# Laser_Tanks_Motherboard_V4.net
KiCad netlist of a schematic drawn in EasyEDA Pro
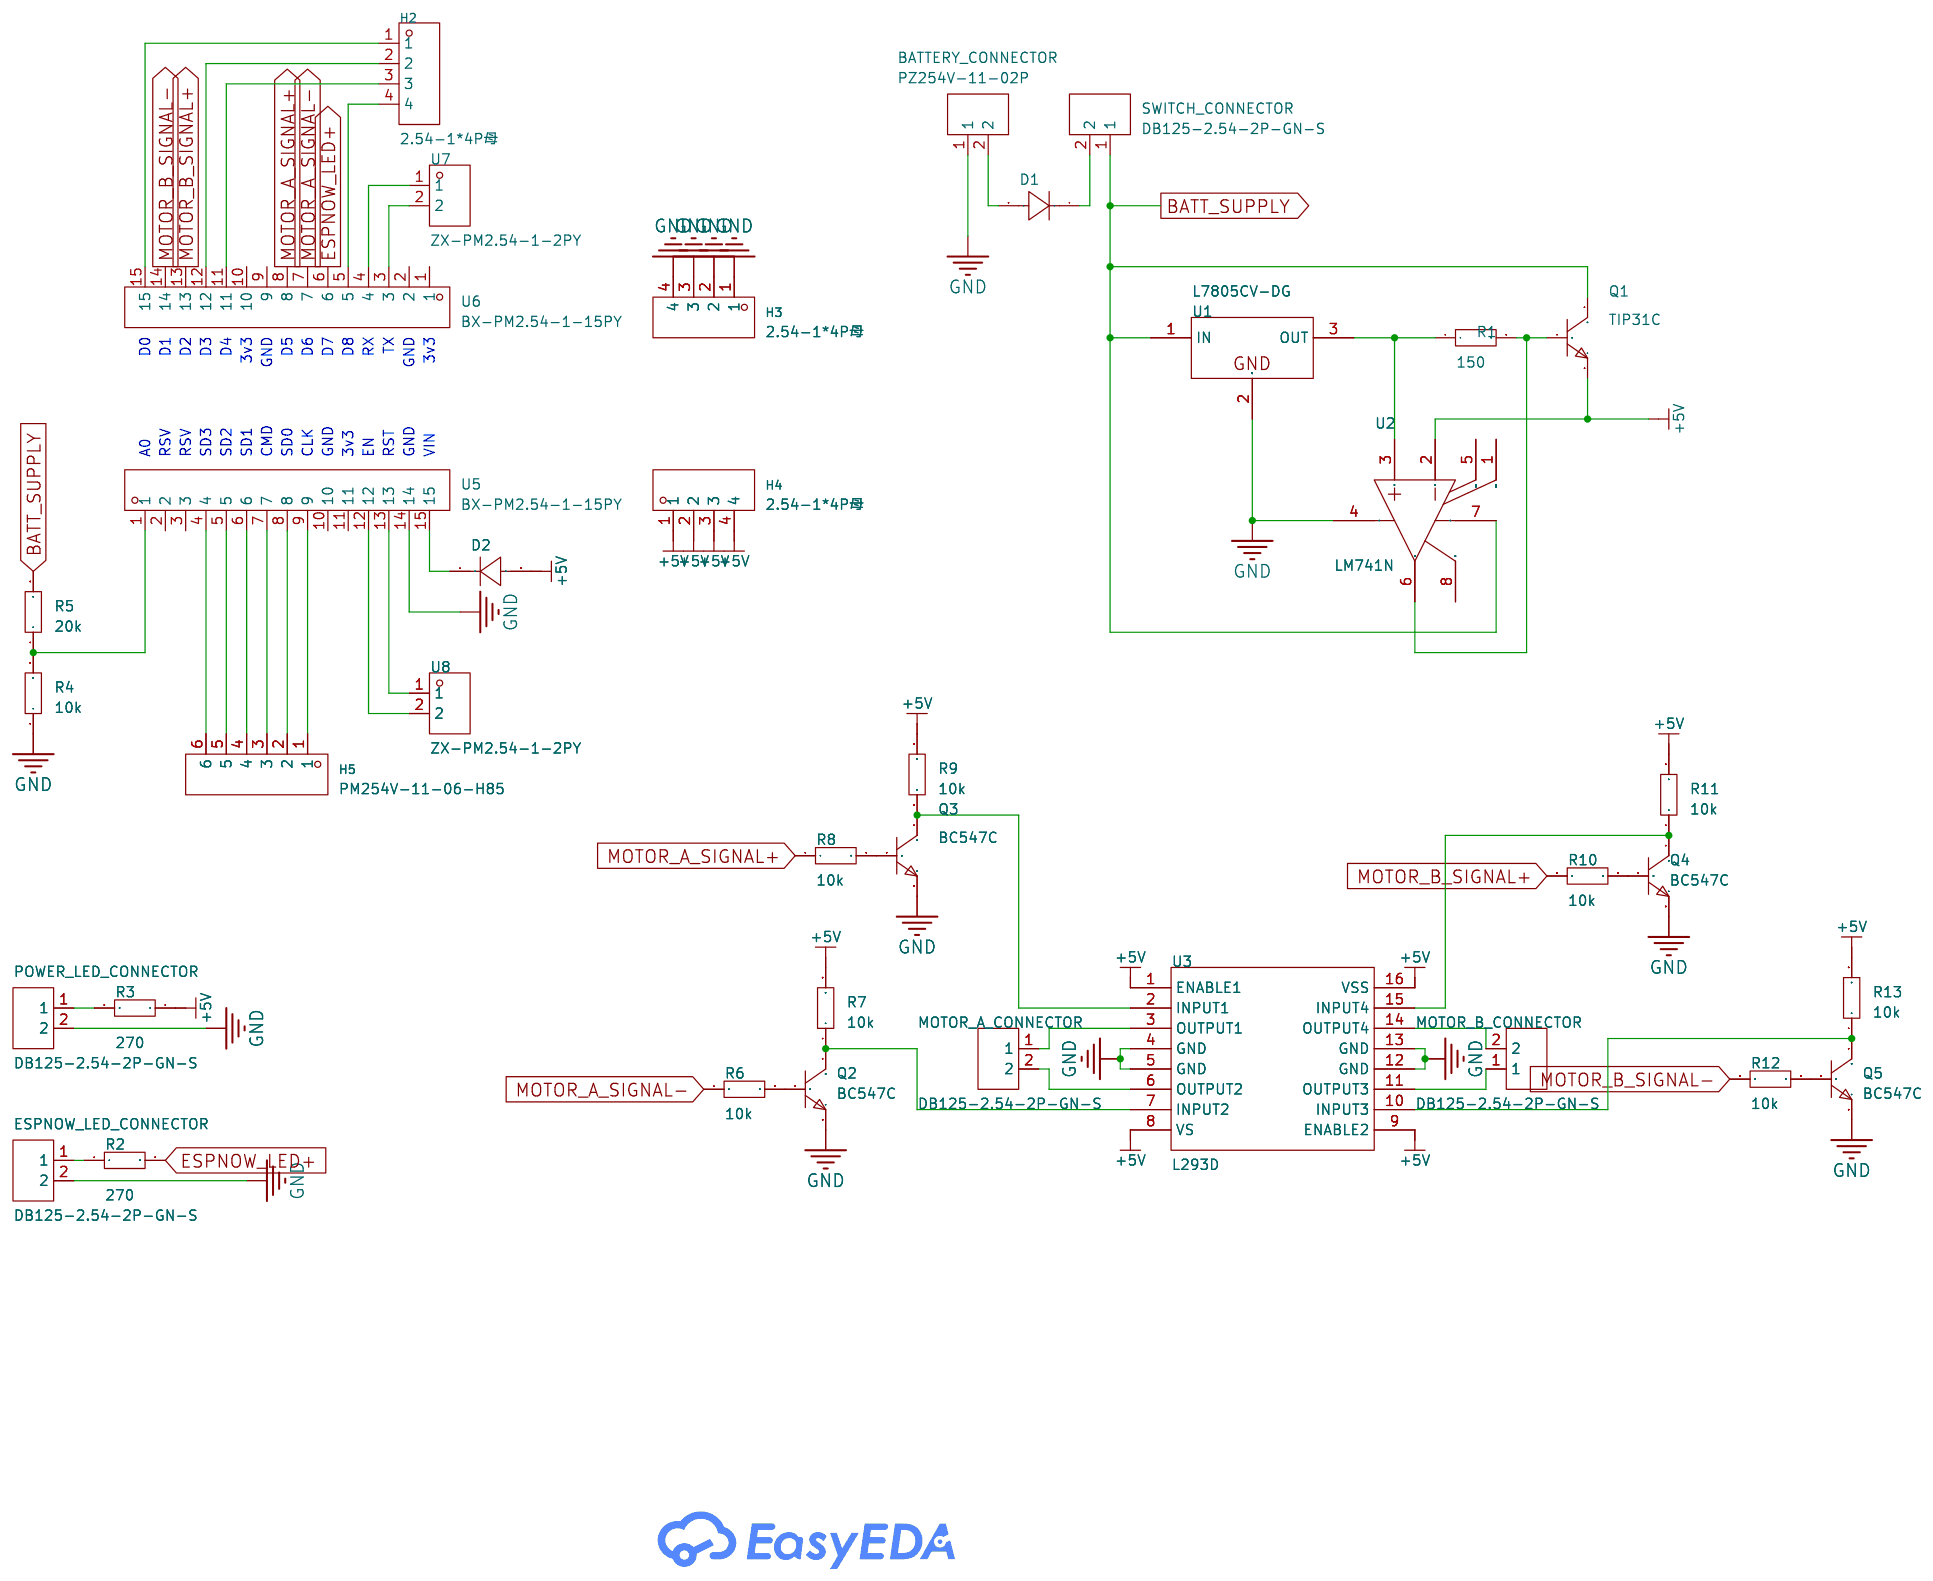
[diagram p0: schematic sheet]

(export (version "E")
  (design (tool "Eeschema 10.0.6"))
  (components
    (comp (ref "BATTERY_CONNECTOR")
      (value "PZ254V-11-02P")
      (footprint "easyedapro:HDR-TH_2P-P2.54-V-M")
      (fields (field (name "Manufacturer") "XFCN(兴飞)"))
      (libsource (lib "easyedapro") (part "PZ254V-11-02P"))
    )
    (comp (ref "D1")
      (value "~")
      (footprint "easyedapro:DO-41_BD2.4-L4.7-P8.70-D0.9-RD")
      (libsource (lib "easyedapro") (part "D_1N4007"))
    )
    (comp (ref "D2")
      (value "~")
      (footprint "easyedapro:DO-41_BD2.4-L4.7-P8.70-D0.9-RD")
      (libsource (lib "easyedapro") (part "D_1N4007"))
    )
    (comp (ref "ESPNOW_LED_CONNECTOR")
      (value "DB125-2.54-2P-GN-S")
      (footprint "easyedapro:CONN-TH_DB125-2.54-2P-GN")
      (fields (field (name "Manufacturer") "DORABO(地博电气)"))
      (libsource (lib "easyedapro") (part "DB125-2.54-2P-GN"))
    )
    (comp (ref "H2")
      (value "2.54-1*4P母")
      (footprint "easyedapro:HDR-TH_4P-P2.54-V-F")
      (fields (field (name "Manufacturer") "BOOMELE(博穆精密)"))
      (libsource (lib "easyedapro") (part "2.54-1*4P母"))
    )
    (comp (ref "H3")
      (value "2.54-1*4P母")
      (footprint "easyedapro:HDR-TH_4P-P2.54-V-F")
      (fields (field (name "Manufacturer") "BOOMELE(博穆精密)"))
      (libsource (lib "easyedapro") (part "2.54-1*4P母"))
    )
    (comp (ref "H4")
      (value "2.54-1*4P母")
      (footprint "easyedapro:HDR-TH_4P-P2.54-V-F")
      (fields (field (name "Manufacturer") "BOOMELE(博穆精密)"))
      (libsource (lib "easyedapro") (part "2.54-1*4P母"))
    )
    (comp (ref "H5")
      (value "PM254V-11-06-H85")
      (footprint "easyedapro:HDR-TH_6P-P2.54-V-F")
      (fields (field (name "Manufacturer") "XFCN(兴飞)"))
      (libsource (lib "easyedapro") (part "PM254V-11-06-H85"))
    )
    (comp (ref "MOTOR_A_CONNECTOR")
      (value "DB125-2.54-2P-GN-S")
      (footprint "easyedapro:CONN-TH_DB125-2.54-2P-GN")
      (fields (field (name "Manufacturer") "DORABO(地博电气)"))
      (libsource (lib "easyedapro") (part "DB125-2.54-2P-GN"))
    )
    (comp (ref "MOTOR_B_CONNECTOR")
      (value "DB125-2.54-2P-GN-S")
      (footprint "easyedapro:CONN-TH_DB125-2.54-2P-GN")
      (fields (field (name "Manufacturer") "DORABO(地博电气)"))
      (libsource (lib "easyedapro") (part "DB125-2.54-2P-GN"))
    )
    (comp (ref "POWER_LED_CONNECTOR")
      (value "DB125-2.54-2P-GN-S")
      (footprint "easyedapro:CONN-TH_DB125-2.54-2P-GN")
      (fields (field (name "Manufacturer") "DORABO(地博电气)"))
      (libsource (lib "easyedapro") (part "DB125-2.54-2P-GN"))
    )
    (comp (ref "Q1")
      (value "TIP31C")
      (footprint "easyedapro:TO-220-3_L10.0-W4.5-P2.54-T")
      (fields (field (name "Manufacturer") "ST(意法半导体)"))
      (libsource (lib "easyedapro") (part "TIP31C"))
    )
    (comp (ref "Q2")
      (value "BC547C")
      (footprint "easyedapro:TO-92-3_L4.9-W3.7-P1.27-L")
      (fields (field (name "Manufacturer") "LGE(鲁光)"))
      (libsource (lib "easyedapro") (part "BC547C"))
    )
    (comp (ref "Q3")
      (value "BC547C")
      (footprint "easyedapro:TO-92-3_L4.9-W3.7-P1.27-L")
      (fields (field (name "Manufacturer") "LGE(鲁光)"))
      (libsource (lib "easyedapro") (part "BC547C"))
    )
    (comp (ref "Q4")
      (value "BC547C")
      (footprint "easyedapro:TO-92-3_L4.9-W3.7-P1.27-L")
      (fields (field (name "Manufacturer") "LGE(鲁光)"))
      (libsource (lib "easyedapro") (part "BC547C"))
    )
    (comp (ref "Q5")
      (value "BC547C")
      (footprint "easyedapro:TO-92-3_L4.9-W3.7-P1.27-L")
      (fields (field (name "Manufacturer") "LGE(鲁光)"))
      (libsource (lib "easyedapro") (part "BC547C"))
    )
    (comp (ref "R1")
      (value "150")
      (footprint "easyedapro:R0603")
      (fields
        (field (name "Manufacturer Part") "MF1/4W-4.7KΩ±1% T")
        (field (name "Manufacturer") "CCO(千志电子)")
      )
      (libsource (lib "easyedapro") (part "Res"))
    )
    (comp (ref "R2")
      (value "270")
      (footprint "easyedapro:R0603")
      (fields
        (field (name "Manufacturer Part") "MF1/4W-4.7KΩ±1% T")
        (field (name "Manufacturer") "CCO(千志电子)")
      )
      (libsource (lib "easyedapro") (part "Res"))
    )
    (comp (ref "R3")
      (value "270")
      (footprint "easyedapro:R0603")
      (fields
        (field (name "Manufacturer Part") "MF1/4W-4.7KΩ±1% T")
        (field (name "Manufacturer") "CCO(千志电子)")
      )
      (libsource (lib "easyedapro") (part "Res"))
    )
    (comp (ref "R4")
      (value "10k")
      (footprint "easyedapro:R0603")
      (fields
        (field (name "Manufacturer Part") "MF1/4W-4.7KΩ±1% T")
        (field (name "Manufacturer") "CCO(千志电子)")
      )
      (libsource (lib "easyedapro") (part "Res"))
    )
    (comp (ref "R5")
      (value "20k")
      (footprint "easyedapro:R0603")
      (fields
        (field (name "Manufacturer Part") "MF1/4W-4.7KΩ±1% T")
        (field (name "Manufacturer") "CCO(千志电子)")
      )
      (libsource (lib "easyedapro") (part "Res"))
    )
    (comp (ref "R6")
      (value "10k")
      (footprint "easyedapro:R0603")
      (fields
        (field (name "Manufacturer Part") "MF1/4W-4.7KΩ±1% T")
        (field (name "Manufacturer") "CCO(千志电子)")
      )
      (libsource (lib "easyedapro") (part "Res"))
    )
    (comp (ref "R7")
      (value "10k")
      (footprint "easyedapro:R0603")
      (fields
        (field (name "Manufacturer Part") "MF1/4W-4.7KΩ±1% T")
        (field (name "Manufacturer") "CCO(千志电子)")
      )
      (libsource (lib "easyedapro") (part "Res"))
    )
    (comp (ref "R8")
      (value "10k")
      (footprint "easyedapro:R0603")
      (fields
        (field (name "Manufacturer Part") "MF1/4W-4.7KΩ±1% T")
        (field (name "Manufacturer") "CCO(千志电子)")
      )
      (libsource (lib "easyedapro") (part "Res"))
    )
    (comp (ref "R9")
      (value "10k")
      (footprint "easyedapro:R0603")
      (fields
        (field (name "Manufacturer Part") "MF1/4W-4.7KΩ±1% T")
        (field (name "Manufacturer") "CCO(千志电子)")
      )
      (libsource (lib "easyedapro") (part "Res"))
    )
    (comp (ref "R10")
      (value "10k")
      (footprint "easyedapro:R0603")
      (fields
        (field (name "Manufacturer Part") "MF1/4W-4.7KΩ±1% T")
        (field (name "Manufacturer") "CCO(千志电子)")
      )
      (libsource (lib "easyedapro") (part "Res"))
    )
    (comp (ref "R11")
      (value "10k")
      (footprint "easyedapro:R0603")
      (fields
        (field (name "Manufacturer Part") "MF1/4W-4.7KΩ±1% T")
        (field (name "Manufacturer") "CCO(千志电子)")
      )
      (libsource (lib "easyedapro") (part "Res"))
    )
    (comp (ref "R12")
      (value "10k")
      (footprint "easyedapro:R0603")
      (fields
        (field (name "Manufacturer Part") "MF1/4W-4.7KΩ±1% T")
        (field (name "Manufacturer") "CCO(千志电子)")
      )
      (libsource (lib "easyedapro") (part "Res"))
    )
    (comp (ref "R13")
      (value "10k")
      (footprint "easyedapro:R0603")
      (fields
        (field (name "Manufacturer Part") "MF1/4W-4.7KΩ±1% T")
        (field (name "Manufacturer") "CCO(千志电子)")
      )
      (libsource (lib "easyedapro") (part "Res"))
    )
    (comp (ref "SWITCH_CONNECTOR")
      (value "DB125-2.54-2P-GN-S")
      (footprint "easyedapro:CONN-TH_DB125-2.54-2P-GN")
      (fields (field (name "Manufacturer") "DORABO(地博电气)"))
      (libsource (lib "easyedapro") (part "DB125-2.54-2P-GN"))
    )
    (comp (ref "U1")
      (value "L7805CV-DG")
      (footprint "easyedapro:TO-220-3_L10.0-W4.5-P2.54-L")
      (fields (field (name "Manufacturer") "ST(意法半导体)"))
      (libsource (lib "easyedapro") (part "L7805CV-DG"))
    )
    (comp (ref "U2")
      (value "LM741N")
      (footprint "easyedapro:DIP-8_L9.3-W6.4-P2.54-LS7.6-BL")
      (fields (field (name "Manufacturer") "HGSEMI(华冠)"))
      (libsource (lib "easyedapro") (part "LM741N"))
    )
    (comp (ref "U3")
      (value "L293D")
      (footprint "easyedapro:DIP-16_L20.0-W6.4-P2.54-LS7.6-BL")
      (fields (field (name "Manufacturer") "ST(意法半导体)"))
      (libsource (lib "easyedapro") (part "L293D"))
    )
    (comp (ref "U5")
      (value "BX-PM2.54-1-15PY")
      (footprint "easyedapro:HDR-TH_15P-P2.54-V-F-1")
      (fields (field (name "Manufacturer") "Bossie(博锡)"))
      (libsource (lib "easyedapro") (part "BX-PM2.54-1-15PY"))
    )
    (comp (ref "U6")
      (value "BX-PM2.54-1-15PY")
      (footprint "easyedapro:HDR-TH_15P-P2.54-V-F-1")
      (fields (field (name "Manufacturer") "Bossie(博锡)"))
      (libsource (lib "easyedapro") (part "BX-PM2.54-1-15PY"))
    )
    (comp (ref "U7")
      (value "ZX-PM2.54-1-2PY")
      (footprint "easyedapro:HDR-TH_2P-P2.54-V-F")
      (fields (field (name "Manufacturer") "Megastar(兆星)"))
      (libsource (lib "easyedapro") (part "ZX-PM2.54-1-2PY"))
    )
    (comp (ref "U8")
      (value "ZX-PM2.54-1-2PY")
      (footprint "easyedapro:HDR-TH_2P-P2.54-V-F")
      (fields (field (name "Manufacturer") "Megastar(兆星)"))
      (libsource (lib "easyedapro") (part "ZX-PM2.54-1-2PY"))
    )
  )
  (nets
    (net (code "1") (name "+5V") (class "Default")
      (node (ref "D2") (pin "2") (pinfunction "A_2") (pintype "input"))
      (node (ref "H4") (pin "1") (pinfunction "1_1") (pintype "input"))
      (node (ref "H4") (pin "2") (pinfunction "2_2") (pintype "input"))
      (node (ref "H4") (pin "3") (pinfunction "3_3") (pintype "input"))
      (node (ref "H4") (pin "4") (pinfunction "4_4") (pintype "input"))
      (node (ref "Q1") (pin "3") (pinfunction "E_3") (pintype "unspecified"))
      (node (ref "R11") (pin "2") (pinfunction "2_2") (pintype "input"))
      (node (ref "R13") (pin "2") (pinfunction "2_2") (pintype "input"))
      (node (ref "R3") (pin "1") (pinfunction "1_1") (pintype "input"))
      (node (ref "R7") (pin "2") (pinfunction "2_2") (pintype "input"))
      (node (ref "R9") (pin "2") (pinfunction "2_2") (pintype "input"))
      (node (ref "U2") (pin "2") (pinfunction "-IN_2") (pintype "unspecified"))
      (node (ref "U3") (pin "1") (pinfunction "ENABLE1_1") (pintype "unspecified"))
      (node (ref "U3") (pin "16") (pinfunction "VSS_16") (pintype "unspecified"))
      (node (ref "U3") (pin "8") (pinfunction "VS_8") (pintype "unspecified"))
      (node (ref "U3") (pin "9") (pinfunction "ENABLE2_9") (pintype "unspecified"))
    )
    (net (code "2") (name "BATT_SUPPLY") (class "Default")
      (node (ref "Q1") (pin "2") (pinfunction "C_2") (pintype "unspecified"))
      (node (ref "R5") (pin "2") (pinfunction "2_2") (pintype "input"))
      (node (ref "SWITCH_CONNECTOR") (pin "1") (pinfunction "1_1") (pintype "unspecified"))
      (node (ref "U1") (pin "1") (pinfunction "IN_1") (pintype "unspecified"))
      (node (ref "U2") (pin "7") (pinfunction "V+_7") (pintype "unspecified"))
    )
    (net (code "3") (name "ESPNOW_LED+") (class "Default")
      (node (ref "R2") (pin "2") (pinfunction "2_2") (pintype "input"))
      (node (ref "U6") (pin "6") (pinfunction "6_6") (pintype "unspecified"))
    )
    (net (code "4") (name "GND") (class "Default")
      (node (ref "BATTERY_CONNECTOR") (pin "1") (pinfunction "1_1") (pintype "unspecified"))
      (node (ref "ESPNOW_LED_CONNECTOR") (pin "2") (pinfunction "2_2") (pintype "unspecified"))
      (node (ref "H3") (pin "1") (pinfunction "1_1") (pintype "input"))
      (node (ref "H3") (pin "2") (pinfunction "2_2") (pintype "input"))
      (node (ref "H3") (pin "3") (pinfunction "3_3") (pintype "input"))
      (node (ref "H3") (pin "4") (pinfunction "4_4") (pintype "input"))
      (node (ref "POWER_LED_CONNECTOR") (pin "2") (pinfunction "2_2") (pintype "unspecified"))
      (node (ref "Q2") (pin "3") (pinfunction "E_3") (pintype "input"))
      (node (ref "Q3") (pin "3") (pinfunction "E_3") (pintype "input"))
      (node (ref "Q4") (pin "3") (pinfunction "E_3") (pintype "input"))
      (node (ref "Q5") (pin "3") (pinfunction "E_3") (pintype "input"))
      (node (ref "R4") (pin "1") (pinfunction "1_1") (pintype "input"))
      (node (ref "U1") (pin "2") (pinfunction "GND_2") (pintype "unspecified"))
      (node (ref "U2") (pin "4") (pinfunction "V-_4") (pintype "unspecified"))
      (node (ref "U3") (pin "12") (pinfunction "GND_12") (pintype "unspecified"))
      (node (ref "U3") (pin "13") (pinfunction "GND_13") (pintype "unspecified"))
      (node (ref "U3") (pin "4") (pinfunction "GND_4") (pintype "unspecified"))
      (node (ref "U3") (pin "5") (pinfunction "GND_5") (pintype "unspecified"))
      (node (ref "U5") (pin "14") (pinfunction "14_14") (pintype "unspecified"))
    )
    (net (code "5") (name "MOTOR_A_SIGNAL+") (class "Default")
      (node (ref "R8") (pin "1") (pinfunction "1_1") (pintype "input"))
      (node (ref "U6") (pin "8") (pinfunction "8_8") (pintype "unspecified"))
    )
    (net (code "6") (name "MOTOR_A_SIGNAL-") (class "Default")
      (node (ref "R6") (pin "1") (pinfunction "1_1") (pintype "input"))
      (node (ref "U6") (pin "7") (pinfunction "7_7") (pintype "unspecified"))
    )
    (net (code "7") (name "MOTOR_B_SIGNAL+") (class "Default")
      (node (ref "R10") (pin "1") (pinfunction "1_1") (pintype "input"))
      (node (ref "U6") (pin "13") (pinfunction "13_13") (pintype "unspecified"))
    )
    (net (code "8") (name "MOTOR_B_SIGNAL-") (class "Default")
      (node (ref "R12") (pin "1") (pinfunction "1_1") (pintype "input"))
      (node (ref "U6") (pin "14") (pinfunction "14_14") (pintype "unspecified"))
    )
    (net (code "9") (name "Net-(D1-A)") (class "Default")
      (node (ref "BATTERY_CONNECTOR") (pin "2") (pinfunction "2_2") (pintype "unspecified"))
      (node (ref "D1") (pin "2") (pinfunction "A_2") (pintype "input"))
    )
    (net (code "10") (name "Net-(D1-K)") (class "Default")
      (node (ref "D1") (pin "1") (pinfunction "K_1") (pintype "input"))
      (node (ref "SWITCH_CONNECTOR") (pin "2") (pinfunction "2_2") (pintype "unspecified"))
    )
    (net (code "11") (name "Net-(D2-K)") (class "Default")
      (node (ref "D2") (pin "1") (pinfunction "K_1") (pintype "input"))
      (node (ref "U5") (pin "15") (pinfunction "15_15") (pintype "unspecified"))
    )
    (net (code "12") (name "Net-(ESPNOW_LED_CONNECTOR-Pad1)") (class "Default")
      (node (ref "ESPNOW_LED_CONNECTOR") (pin "1") (pinfunction "1_1") (pintype "unspecified"))
      (node (ref "R2") (pin "1") (pinfunction "1_1") (pintype "input"))
    )
    (net (code "13") (name "Net-(H2-Pad1)") (class "Default")
      (node (ref "H2") (pin "1") (pinfunction "1_1") (pintype "input"))
      (node (ref "U6") (pin "15") (pinfunction "15_15") (pintype "unspecified"))
    )
    (net (code "14") (name "Net-(H2-Pad2)") (class "Default")
      (node (ref "H2") (pin "2") (pinfunction "2_2") (pintype "input"))
      (node (ref "U6") (pin "12") (pinfunction "12_12") (pintype "unspecified"))
    )
    (net (code "15") (name "Net-(H2-Pad3)") (class "Default")
      (node (ref "H2") (pin "3") (pinfunction "3_3") (pintype "input"))
      (node (ref "U6") (pin "11") (pinfunction "11_11") (pintype "unspecified"))
    )
    (net (code "16") (name "Net-(H2-Pad4)") (class "Default")
      (node (ref "H2") (pin "4") (pinfunction "4_4") (pintype "input"))
      (node (ref "U6") (pin "5") (pinfunction "5_5") (pintype "unspecified"))
    )
    (net (code "17") (name "Net-(H5-Pad1)") (class "Default")
      (node (ref "H5") (pin "1") (pinfunction "1_1") (pintype "input"))
      (node (ref "U5") (pin "9") (pinfunction "9_9") (pintype "unspecified"))
    )
    (net (code "18") (name "Net-(H5-Pad2)") (class "Default")
      (node (ref "H5") (pin "2") (pinfunction "2_2") (pintype "input"))
      (node (ref "U5") (pin "8") (pinfunction "8_8") (pintype "unspecified"))
    )
    (net (code "19") (name "Net-(H5-Pad3)") (class "Default")
      (node (ref "H5") (pin "3") (pinfunction "3_3") (pintype "input"))
      (node (ref "U5") (pin "7") (pinfunction "7_7") (pintype "unspecified"))
    )
    (net (code "20") (name "Net-(H5-Pad4)") (class "Default")
      (node (ref "H5") (pin "4") (pinfunction "4_4") (pintype "input"))
      (node (ref "U5") (pin "6") (pinfunction "6_6") (pintype "unspecified"))
    )
    (net (code "21") (name "Net-(H5-Pad5)") (class "Default")
      (node (ref "H5") (pin "5") (pinfunction "5_5") (pintype "input"))
      (node (ref "U5") (pin "5") (pinfunction "5_5") (pintype "unspecified"))
    )
    (net (code "22") (name "Net-(H5-Pad6)") (class "Default")
      (node (ref "H5") (pin "6") (pinfunction "6_6") (pintype "input"))
      (node (ref "U5") (pin "4") (pinfunction "4_4") (pintype "unspecified"))
    )
    (net (code "23") (name "Net-(POWER_LED_CONNECTOR-Pad1)") (class "Default")
      (node (ref "POWER_LED_CONNECTOR") (pin "1") (pinfunction "1_1") (pintype "unspecified"))
      (node (ref "R3") (pin "2") (pinfunction "2_2") (pintype "input"))
    )
    (net (code "24") (name "Net-(Q1-B)") (class "Default")
      (node (ref "Q1") (pin "1") (pinfunction "B_1") (pintype "unspecified"))
      (node (ref "R1") (pin "2") (pinfunction "2_2") (pintype "input"))
      (node (ref "U2") (pin "6") (pinfunction "OUT_6") (pintype "output"))
    )
    (net (code "25") (name "Net-(Q2-B)") (class "Default")
      (node (ref "Q2") (pin "2") (pinfunction "B_2") (pintype "input"))
      (node (ref "R6") (pin "2") (pinfunction "2_2") (pintype "input"))
    )
    (net (code "26") (name "Net-(Q2-C)") (class "Default")
      (node (ref "Q2") (pin "1") (pinfunction "C_1") (pintype "input"))
      (node (ref "R7") (pin "1") (pinfunction "1_1") (pintype "input"))
      (node (ref "U3") (pin "7") (pinfunction "INPUT2_7") (pintype "unspecified"))
    )
    (net (code "27") (name "Net-(Q3-B)") (class "Default")
      (node (ref "Q3") (pin "2") (pinfunction "B_2") (pintype "input"))
      (node (ref "R8") (pin "2") (pinfunction "2_2") (pintype "input"))
    )
    (net (code "28") (name "Net-(Q3-C)") (class "Default")
      (node (ref "Q3") (pin "1") (pinfunction "C_1") (pintype "input"))
      (node (ref "R9") (pin "1") (pinfunction "1_1") (pintype "input"))
      (node (ref "U3") (pin "2") (pinfunction "INPUT1_2") (pintype "unspecified"))
    )
    (net (code "29") (name "Net-(Q4-B)") (class "Default")
      (node (ref "Q4") (pin "2") (pinfunction "B_2") (pintype "input"))
      (node (ref "R10") (pin "2") (pinfunction "2_2") (pintype "input"))
    )
    (net (code "30") (name "Net-(Q4-C)") (class "Default")
      (node (ref "Q4") (pin "1") (pinfunction "C_1") (pintype "input"))
      (node (ref "R11") (pin "1") (pinfunction "1_1") (pintype "input"))
      (node (ref "U3") (pin "15") (pinfunction "INPUT4_15") (pintype "unspecified"))
    )
    (net (code "31") (name "Net-(Q5-B)") (class "Default")
      (node (ref "Q5") (pin "2") (pinfunction "B_2") (pintype "input"))
      (node (ref "R12") (pin "2") (pinfunction "2_2") (pintype "input"))
    )
    (net (code "32") (name "Net-(Q5-C)") (class "Default")
      (node (ref "Q5") (pin "1") (pinfunction "C_1") (pintype "input"))
      (node (ref "R13") (pin "1") (pinfunction "1_1") (pintype "input"))
      (node (ref "U3") (pin "10") (pinfunction "INPUT3_10") (pintype "unspecified"))
    )
    (net (code "33") (name "Net-(R4-Pad2)") (class "Default")
      (node (ref "R4") (pin "2") (pinfunction "2_2") (pintype "input"))
      (node (ref "R5") (pin "1") (pinfunction "1_1") (pintype "input"))
      (node (ref "U5") (pin "1") (pinfunction "1_1") (pintype "unspecified"))
    )
    (net (code "34") (name "Net-(U1-OUT)") (class "Default")
      (node (ref "R1") (pin "1") (pinfunction "1_1") (pintype "input"))
      (node (ref "U1") (pin "3") (pinfunction "OUT_3") (pintype "unspecified"))
      (node (ref "U2") (pin "3") (pinfunction "+IN_3") (pintype "unspecified"))
    )
    (net (code "35") (name "Net-(U3-OUTPUT1)") (class "Default")
      (node (ref "MOTOR_A_CONNECTOR") (pin "1") (pinfunction "1_1") (pintype "unspecified"))
      (node (ref "U3") (pin "3") (pinfunction "OUTPUT1_3") (pintype "unspecified"))
    )
    (net (code "36") (name "Net-(U3-OUTPUT2)") (class "Default")
      (node (ref "MOTOR_A_CONNECTOR") (pin "2") (pinfunction "2_2") (pintype "unspecified"))
      (node (ref "U3") (pin "6") (pinfunction "OUTPUT2_6") (pintype "unspecified"))
    )
    (net (code "37") (name "Net-(U3-OUTPUT3)") (class "Default")
      (node (ref "MOTOR_B_CONNECTOR") (pin "1") (pinfunction "1_1") (pintype "unspecified"))
      (node (ref "U3") (pin "11") (pinfunction "OUTPUT3_11") (pintype "unspecified"))
    )
    (net (code "38") (name "Net-(U3-OUTPUT4)") (class "Default")
      (node (ref "MOTOR_B_CONNECTOR") (pin "2") (pinfunction "2_2") (pintype "unspecified"))
      (node (ref "U3") (pin "14") (pinfunction "OUTPUT4_14") (pintype "unspecified"))
    )
    (net (code "39") (name "Net-(U5-Pad12)") (class "Default")
      (node (ref "U5") (pin "12") (pinfunction "12_12") (pintype "unspecified"))
      (node (ref "U8") (pin "2") (pinfunction "2_2") (pintype "unspecified"))
    )
    (net (code "40") (name "Net-(U5-Pad13)") (class "Default")
      (node (ref "U5") (pin "13") (pinfunction "13_13") (pintype "unspecified"))
      (node (ref "U8") (pin "1") (pinfunction "1_1") (pintype "unspecified"))
    )
    (net (code "41") (name "Net-(U6-Pad3)") (class "Default")
      (node (ref "U6") (pin "3") (pinfunction "3_3") (pintype "unspecified"))
      (node (ref "U7") (pin "2") (pinfunction "2_2") (pintype "unspecified"))
    )
    (net (code "42") (name "Net-(U6-Pad4)") (class "Default")
      (node (ref "U6") (pin "4") (pinfunction "4_4") (pintype "unspecified"))
      (node (ref "U7") (pin "1") (pinfunction "1_1") (pintype "unspecified"))
    )
    (net (code "43") (name "unconnected-(U2-NC-Pad8)") (class "Default")
      (node (ref "U2") (pin "8") (pinfunction "NC_8") (pintype "unspecified"))
    )
    (net (code "44") (name "unconnected-(U2-OFFSET_NULL-Pad1)") (class "Default")
      (node (ref "U2") (pin "1") (pinfunction "OFFSET_NULL_1") (pintype "unspecified"))
    )
    (net (code "45") (name "unconnected-(U2-OFFSET_NULL-Pad5)") (class "Default")
      (node (ref "U2") (pin "5") (pinfunction "OFFSET_NULL_5") (pintype "unspecified"))
    )
    (net (code "46") (name "unconnected-(U5-Pad2)") (class "Default")
      (node (ref "U5") (pin "2") (pinfunction "2_2") (pintype "unspecified"))
    )
    (net (code "47") (name "unconnected-(U5-Pad3)") (class "Default")
      (node (ref "U5") (pin "3") (pinfunction "3_3") (pintype "unspecified"))
    )
    (net (code "48") (name "unconnected-(U5-Pad10)") (class "Default")
      (node (ref "U5") (pin "10") (pinfunction "10_10") (pintype "unspecified"))
    )
    (net (code "49") (name "unconnected-(U5-Pad11)") (class "Default")
      (node (ref "U5") (pin "11") (pinfunction "11_11") (pintype "unspecified"))
    )
    (net (code "50") (name "unconnected-(U6-Pad1)") (class "Default")
      (node (ref "U6") (pin "1") (pinfunction "1_1") (pintype "unspecified"))
    )
    (net (code "51") (name "unconnected-(U6-Pad2)") (class "Default")
      (node (ref "U6") (pin "2") (pinfunction "2_2") (pintype "unspecified"))
    )
    (net (code "52") (name "unconnected-(U6-Pad9)") (class "Default")
      (node (ref "U6") (pin "9") (pinfunction "9_9") (pintype "unspecified"))
    )
    (net (code "53") (name "unconnected-(U6-Pad10)") (class "Default")
      (node (ref "U6") (pin "10") (pinfunction "10_10") (pintype "unspecified"))
    )
  )
)
